# Speaker_SMD.net
KiCad netlist of a schematic drawn in EAGLE
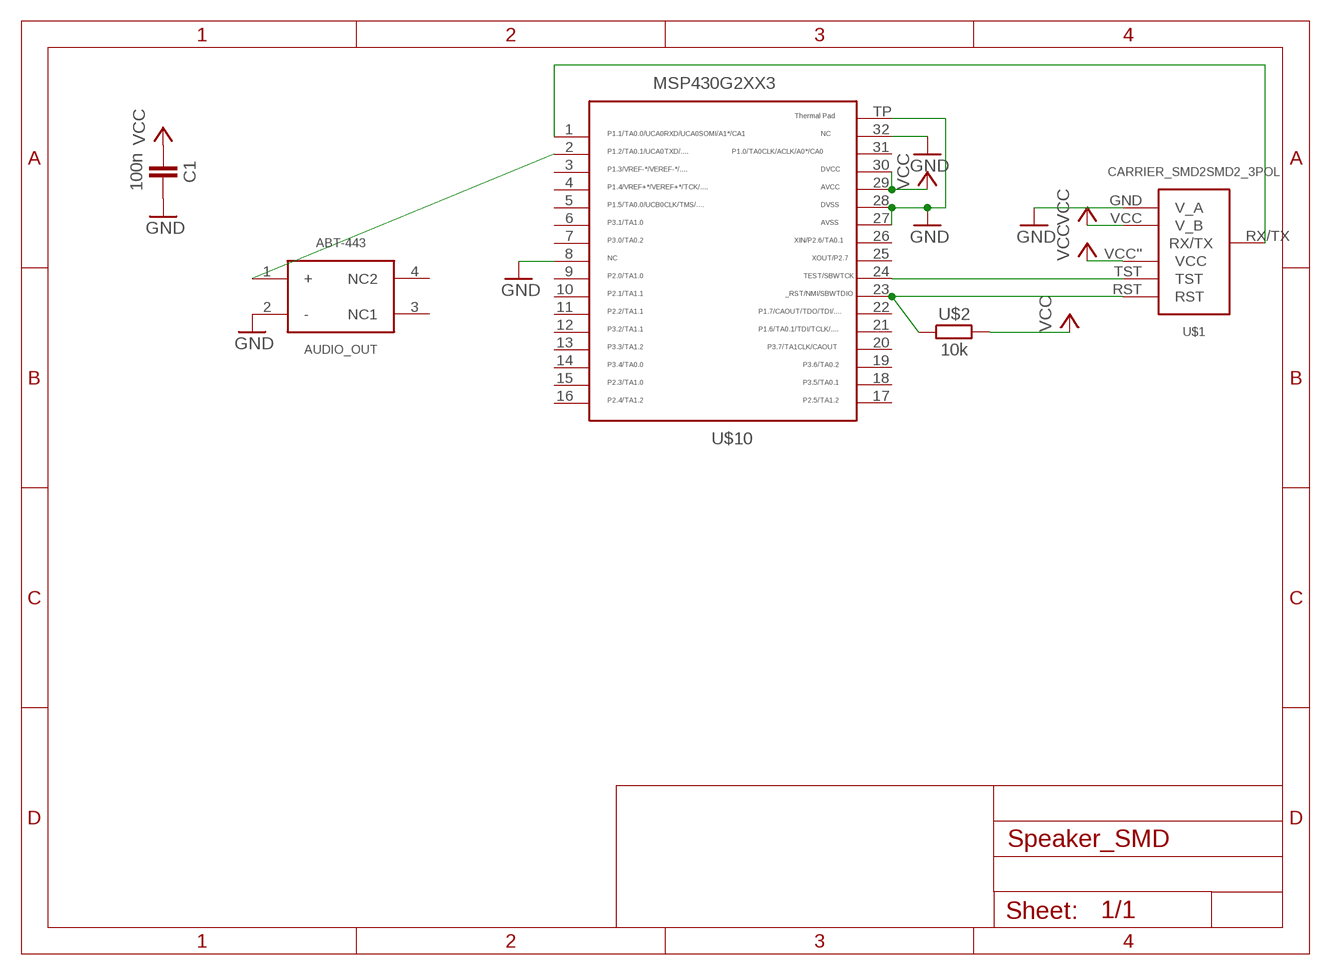
[diagram p0: schematic, sheet 1]

(export (version "E")
  (design (tool "Eeschema 10.0.6"))
  (components
    (comp (ref "AUDIO_OUT")
      (value "ABT-443")
      (footprint "eagle-import:ABT-443-RC")
      (libsource (lib "eagle-import") (part "ABT-443"))
    )
    (comp (ref "C1")
      (value "100n")
      (footprint "eagle-import:603")
      (libsource (lib "eagle-import") (part "CAPACITOR"))
    )
    (comp (ref "U$1")
      (value "CARRIER_SMD2SMD2_3POL")
      (footprint "eagle-import:CARRIER_SMD2_3POL")
      (libsource (lib "eagle-import") (part "CARRIER_SMD2SMD2_3POL"))
    )
    (comp (ref "U$2")
      (value "10k")
      (footprint "eagle-import:603")
      (libsource (lib "eagle-import") (part "RESISTOR0603"))
    )
    (comp (ref "U$10")
      (value "MSP430G2553")
      (footprint "eagle-import:QFN32")
      (libsource (lib "eagle-import") (part "MSP430G2553"))
    )
  )
  (nets
    (net (code "1") (name "GND") (class "Default")
      (node (ref "AUDIO_OUT") (pin "2") (pinfunction "-_2") (pintype "bidirectional"))
      (node (ref "C1") (pin "2") (pinfunction "2_2") (pintype "passive"))
      (node (ref "U$1") (pin "GND") (pinfunction "V_A_GND") (pintype "bidirectional"))
      (node (ref "U$10") (pin "27") (pinfunction "27_27") (pintype "bidirectional"))
      (node (ref "U$10") (pin "28") (pinfunction "28_28") (pintype "bidirectional"))
      (node (ref "U$10") (pin "32") (pinfunction "32_32") (pintype "bidirectional"))
      (node (ref "U$10") (pin "8") (pinfunction "8_8") (pintype "bidirectional"))
      (node (ref "U$10") (pin "TP") (pinfunction "TP_TP") (pintype "bidirectional"))
    )
    (net (code "2") (name "Net-(AUDIO_OUT-+)") (class "Default")
      (node (ref "AUDIO_OUT") (pin "1") (pinfunction "+_1") (pintype "bidirectional"))
      (node (ref "U$10") (pin "2") (pinfunction "2_2") (pintype "bidirectional"))
    )
    (net (code "3") (name "Net-(U$1-PadRST)") (class "Default")
      (node (ref "U$1") (pin "RST") (pinfunction "RST_RST") (pintype "bidirectional"))
      (node (ref "U$10") (pin "23") (pinfunction "23_23") (pintype "bidirectional"))
      (node (ref "U$2") (pin "1") (pinfunction "1_1") (pintype "passive"))
    )
    (net (code "4") (name "Net-(U$1-PadRX{slash}TX)") (class "Default")
      (node (ref "U$1") (pin "RX/TX") (pinfunction "RX/TX_RX/TX") (pintype "bidirectional"))
      (node (ref "U$10") (pin "1") (pinfunction "1_1") (pintype "bidirectional"))
    )
    (net (code "5") (name "Net-(U$1-PadTST)") (class "Default")
      (node (ref "U$1") (pin "TST") (pinfunction "TST_TST") (pintype "bidirectional"))
      (node (ref "U$10") (pin "24") (pinfunction "24_24") (pintype "bidirectional"))
    )
    (net (code "6") (name "VCC") (class "Default")
      (node (ref "C1") (pin "1") (pinfunction "1_1") (pintype "passive"))
      (node (ref "U$1") (pin "VCC") (pinfunction "V_B_VCC") (pintype "bidirectional"))
      (node (ref "U$1") (pin "VCC''") (pinfunction "VCC_VCC''") (pintype "bidirectional"))
      (node (ref "U$10") (pin "29") (pinfunction "29_29") (pintype "bidirectional"))
      (node (ref "U$10") (pin "30") (pinfunction "30_30") (pintype "bidirectional"))
      (node (ref "U$2") (pin "2") (pinfunction "2_2") (pintype "passive"))
    )
    (net (code "7") (name "unconnected-(AUDIO_OUT-NC1-Pad3)") (class "Default")
      (node (ref "AUDIO_OUT") (pin "3") (pinfunction "NC1_3") (pintype "bidirectional"))
    )
    (net (code "8") (name "unconnected-(AUDIO_OUT-NC2-Pad4)") (class "Default")
      (node (ref "AUDIO_OUT") (pin "4") (pinfunction "NC2_4") (pintype "bidirectional"))
    )
    (net (code "9") (name "unconnected-(U$10-Pad3)") (class "Default")
      (node (ref "U$10") (pin "3") (pinfunction "3_3") (pintype "bidirectional"))
    )
    (net (code "10") (name "unconnected-(U$10-Pad4)") (class "Default")
      (node (ref "U$10") (pin "4") (pinfunction "4_4") (pintype "bidirectional"))
    )
    (net (code "11") (name "unconnected-(U$10-Pad5)") (class "Default")
      (node (ref "U$10") (pin "5") (pinfunction "5_5") (pintype "bidirectional"))
    )
    (net (code "12") (name "unconnected-(U$10-Pad6)") (class "Default")
      (node (ref "U$10") (pin "6") (pinfunction "6_6") (pintype "bidirectional"))
    )
    (net (code "13") (name "unconnected-(U$10-Pad7)") (class "Default")
      (node (ref "U$10") (pin "7") (pinfunction "7_7") (pintype "bidirectional"))
    )
    (net (code "14") (name "unconnected-(U$10-Pad9)") (class "Default")
      (node (ref "U$10") (pin "9") (pinfunction "9_9") (pintype "bidirectional"))
    )
    (net (code "15") (name "unconnected-(U$10-Pad10)") (class "Default")
      (node (ref "U$10") (pin "10") (pinfunction "10_10") (pintype "bidirectional"))
    )
    (net (code "16") (name "unconnected-(U$10-Pad11)") (class "Default")
      (node (ref "U$10") (pin "11") (pinfunction "11_11") (pintype "bidirectional"))
    )
    (net (code "17") (name "unconnected-(U$10-Pad12)") (class "Default")
      (node (ref "U$10") (pin "12") (pinfunction "12_12") (pintype "bidirectional"))
    )
    (net (code "18") (name "unconnected-(U$10-Pad13)") (class "Default")
      (node (ref "U$10") (pin "13") (pinfunction "13_13") (pintype "bidirectional"))
    )
    (net (code "19") (name "unconnected-(U$10-Pad14)") (class "Default")
      (node (ref "U$10") (pin "14") (pinfunction "14_14") (pintype "bidirectional"))
    )
    (net (code "20") (name "unconnected-(U$10-Pad15)") (class "Default")
      (node (ref "U$10") (pin "15") (pinfunction "15_15") (pintype "bidirectional"))
    )
    (net (code "21") (name "unconnected-(U$10-Pad16)") (class "Default")
      (node (ref "U$10") (pin "16") (pinfunction "16_16") (pintype "bidirectional"))
    )
    (net (code "22") (name "unconnected-(U$10-Pad17)") (class "Default")
      (node (ref "U$10") (pin "17") (pinfunction "17_17") (pintype "bidirectional"))
    )
    (net (code "23") (name "unconnected-(U$10-Pad18)") (class "Default")
      (node (ref "U$10") (pin "18") (pinfunction "18_18") (pintype "bidirectional"))
    )
    (net (code "24") (name "unconnected-(U$10-Pad19)") (class "Default")
      (node (ref "U$10") (pin "19") (pinfunction "19_19") (pintype "bidirectional"))
    )
    (net (code "25") (name "unconnected-(U$10-Pad20)") (class "Default")
      (node (ref "U$10") (pin "20") (pinfunction "20_20") (pintype "bidirectional"))
    )
    (net (code "26") (name "unconnected-(U$10-Pad21)") (class "Default")
      (node (ref "U$10") (pin "21") (pinfunction "21_21") (pintype "bidirectional"))
    )
    (net (code "27") (name "unconnected-(U$10-Pad22)") (class "Default")
      (node (ref "U$10") (pin "22") (pinfunction "22_22") (pintype "bidirectional"))
    )
    (net (code "28") (name "unconnected-(U$10-Pad25)") (class "Default")
      (node (ref "U$10") (pin "25") (pinfunction "25_25") (pintype "bidirectional"))
    )
    (net (code "29") (name "unconnected-(U$10-Pad26)") (class "Default")
      (node (ref "U$10") (pin "26") (pinfunction "26_26") (pintype "bidirectional"))
    )
    (net (code "30") (name "unconnected-(U$10-Pad31)") (class "Default")
      (node (ref "U$10") (pin "31") (pinfunction "31_31") (pintype "bidirectional"))
    )
  )
)
